# Hooly_2_022.net
KiCad netlist of a schematic drawn in EAGLE
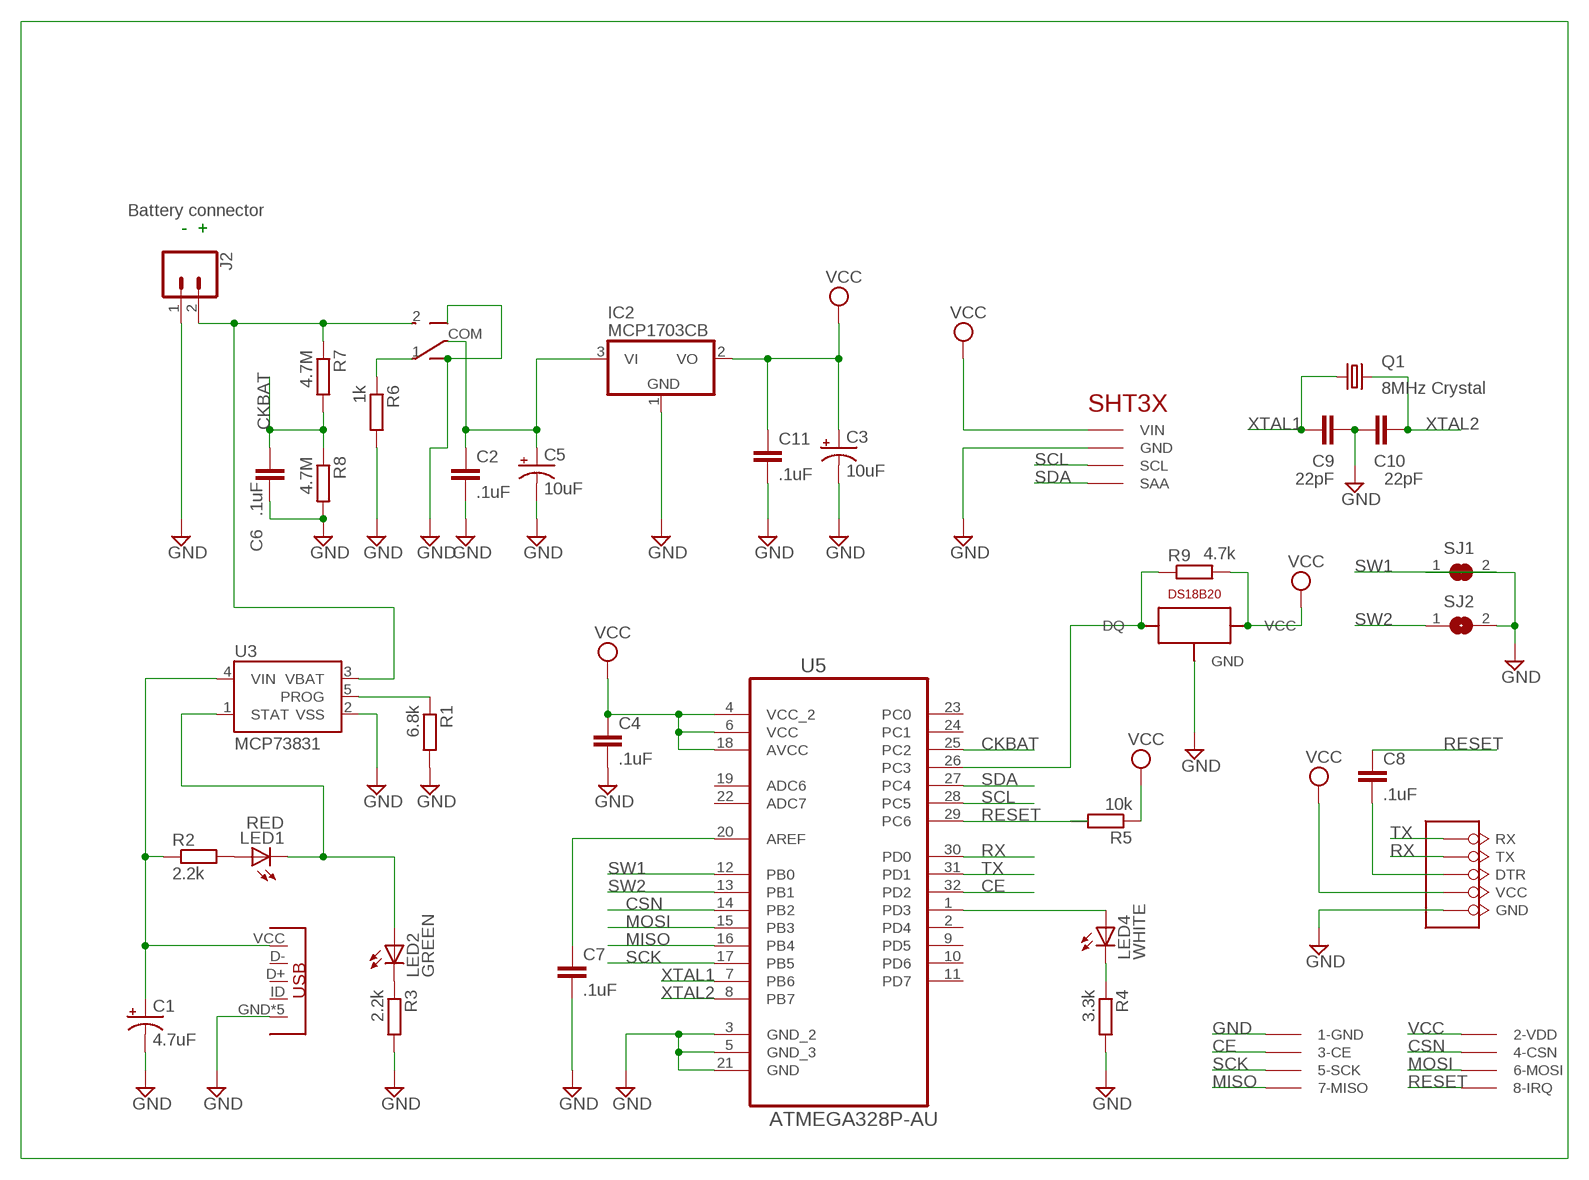
[diagram p0: schematic, sheet 1]

(export (version "E")
  (design (tool "Eeschema 10.0.6"))
  (components
    (comp (ref "C1")
      (value "4.7uF")
      (footprint "eagle-import:CPOL-RADIAL-2.5MM-5MM")
      (libsource (lib "eagle-import") (part "10UF-POLAR-RADIAL-2.5MM-25V-20%"))
    )
    (comp (ref "C2")
      (value ".1uF")
      (footprint "eagle-import:C1206")
      (libsource (lib "eagle-import") (part "resistor_348_C-EUC1206"))
    )
    (comp (ref "C3")
      (value "10uF")
      (footprint "eagle-import:CPOL-RADIAL-2.5MM-5MM")
      (libsource (lib "eagle-import") (part "10UF-POLAR-RADIAL-2.5MM-25V-20%"))
    )
    (comp (ref "C4")
      (value ".1uF")
      (footprint "eagle-import:C1206")
      (libsource (lib "eagle-import") (part "resistor_348_C-EUC1206"))
    )
    (comp (ref "C5")
      (value "10uF")
      (footprint "eagle-import:CPOL-RADIAL-2.5MM-5MM")
      (libsource (lib "eagle-import") (part "10UF-POLAR-RADIAL-2.5MM-25V-20%"))
    )
    (comp (ref "C6")
      (value ".1uF")
      (footprint "eagle-import:C1206")
      (libsource (lib "eagle-import") (part "resistor_348_C-EUC1206"))
    )
    (comp (ref "C7")
      (value ".1uF")
      (footprint "eagle-import:C1206")
      (libsource (lib "eagle-import") (part "resistor_348_C-EUC1206"))
    )
    (comp (ref "C8")
      (value ".1uF")
      (footprint "eagle-import:C1206")
      (libsource (lib "eagle-import") (part "resistor_348_C-EUC1206"))
    )
    (comp (ref "C9")
      (value "22pF")
      (footprint "eagle-import:C0603K")
      (libsource (lib "eagle-import") (part "C-EUC0603K"))
    )
    (comp (ref "C10")
      (value "22pF")
      (footprint "eagle-import:C0603K")
      (libsource (lib "eagle-import") (part "C-EUC0603K"))
    )
    (comp (ref "C11")
      (value ".1uF")
      (footprint "eagle-import:C1206")
      (libsource (lib "eagle-import") (part "resistor_348_C-EUC1206"))
    )
    (comp (ref "IC2")
      (value "MCP1703CB")
      (footprint "eagle-import:SOT23")
      (libsource (lib "eagle-import") (part "MCP1703CB"))
    )
    (comp (ref "J2")
      (value "CONN_02")
      (footprint "eagle-import:1X02")
      (libsource (lib "eagle-import") (part "CONN_02"))
    )
    (comp (ref "LED1")
      (value "RED")
      (footprint "eagle-import:CHIPLED_1206")
      (libsource (lib "eagle-import") (part "LEDCHIPLED_1206"))
    )
    (comp (ref "LED2")
      (value "GREEN")
      (footprint "eagle-import:CHIPLED_1206")
      (libsource (lib "eagle-import") (part "LEDCHIPLED_1206"))
    )
    (comp (ref "LED4")
      (value "WHITE")
      (footprint "eagle-import:CHIPLED_1206")
      (libsource (lib "eagle-import") (part "LEDCHIPLED_1206"))
    )
    (comp (ref "Q1")
      (value "8MHz Crystal")
      (footprint "eagle-import:5.0X3.2_2")
      (libsource (lib "eagle-import") (part "KX-9B"))
    )
    (comp (ref "R1")
      (value "6.8k")
      (footprint "eagle-import:R1206")
      (libsource (lib "eagle-import") (part "R-EU_R1206"))
    )
    (comp (ref "R2")
      (value "2.2k")
      (footprint "eagle-import:R1206")
      (libsource (lib "eagle-import") (part "R-EU_R1206"))
    )
    (comp (ref "R3")
      (value "2.2k")
      (footprint "eagle-import:R1206")
      (libsource (lib "eagle-import") (part "R-EU_R1206"))
    )
    (comp (ref "R4")
      (value "3.3k")
      (footprint "eagle-import:R1206")
      (libsource (lib "eagle-import") (part "R-EU_R1206"))
    )
    (comp (ref "R5")
      (value "10k")
      (footprint "eagle-import:R1206")
      (libsource (lib "eagle-import") (part "R-EU_R1206"))
    )
    (comp (ref "R6")
      (value "1k")
      (footprint "eagle-import:R1206")
      (libsource (lib "eagle-import") (part "R-EU_R1206"))
    )
    (comp (ref "R7")
      (value "4.7M")
      (footprint "eagle-import:R1206")
      (libsource (lib "eagle-import") (part "R-EU_R1206"))
    )
    (comp (ref "R8")
      (value "4.7M")
      (footprint "eagle-import:R1206")
      (libsource (lib "eagle-import") (part "R-EU_R1206"))
    )
    (comp (ref "R9")
      (value "4.7k")
      (footprint "eagle-import:R1206")
      (libsource (lib "eagle-import") (part "R-EU_R1206"))
    )
    (comp (ref "SJ1") (value "SJ") (footprint "eagle-import:SJ") (libsource (lib "eagle-import") (part "SJ")))
    (comp (ref "SJ2") (value "SJ") (footprint "eagle-import:SJ") (libsource (lib "eagle-import") (part "SJ")))
    (comp (ref "U$1")
      (value "SHT3XLARGE")
      (footprint "eagle-import:MYSHT3X")
      (libsource (lib "eagle-import") (part "SHT3XLARGE"))
    )
    (comp (ref "U$2")
      (value "MYSWITCH2MM")
      (footprint "eagle-import:MYSWITCH")
      (libsource (lib "eagle-import") (part "MYSWITCH2MM"))
    )
    (comp (ref "U$3")
      (value "MYDS18B20")
      (footprint "eagle-import:MYDS18B20")
      (libsource (lib "eagle-import") (part "MYDS18B20"))
    )
    (comp (ref "U$4")
      (value "MYNRF24L01SOCKET")
      (footprint "eagle-import:MYNRF24L01SOCKET")
      (libsource (lib "eagle-import") (part "MYNRF24L01SOCKET"))
    )
    (comp (ref "U$6")
      (value "FTDI232")
      (footprint "eagle-import:FTDI232")
      (libsource (lib "eagle-import") (part "FTDI232"))
    )
    (comp (ref "U$7")
      (value "MYMICROUSB")
      (footprint "eagle-import:MYMICROUSB")
      (libsource (lib "eagle-import") (part "MYMICROUSB"))
    )
    (comp (ref "U3")
      (value "MCP73831")
      (footprint "eagle-import:SOT23-5")
      (libsource (lib "eagle-import") (part "MCP73831"))
    )
    (comp (ref "U5")
      (value "ATMEGA328P-AU")
      (footprint "eagle-import:QFP80P900X900X120-32N")
      (libsource (lib "eagle-import") (part "ATMEGA328P-AU"))
    )
  )
  (nets
    (net (code "1") (name "/CE") (class "Default")
      (node (ref "U$4") (pin "CE") (pinfunction "3-CE_CE") (pintype "bidirectional"))
      (node (ref "U5") (pin "32") (pinfunction "PD2_32") (pintype "bidirectional"))
    )
    (net (code "2") (name "/CKBAT") (class "Default")
      (node (ref "C6") (pin "1") (pinfunction "1_1") (pintype "passive"))
      (node (ref "R7") (pin "2") (pinfunction "2_2") (pintype "passive"))
      (node (ref "R8") (pin "1") (pinfunction "1_1") (pintype "passive"))
      (node (ref "U5") (pin "25") (pinfunction "PC2_25") (pintype "bidirectional"))
    )
    (net (code "3") (name "/CSN") (class "Default")
      (node (ref "U$4") (pin "CSN") (pinfunction "4-CSN_CSN") (pintype "bidirectional"))
      (node (ref "U5") (pin "14") (pinfunction "PB2_14") (pintype "bidirectional"))
    )
    (net (code "4") (name "/MISO") (class "Default")
      (node (ref "U$4") (pin "MISO") (pinfunction "7-MISO_MISO") (pintype "bidirectional"))
      (node (ref "U5") (pin "16") (pinfunction "PB4_16") (pintype "bidirectional"))
    )
    (net (code "5") (name "/MOSI") (class "Default")
      (node (ref "U$4") (pin "MOSI") (pinfunction "6-MOSI_MOSI") (pintype "bidirectional"))
      (node (ref "U5") (pin "15") (pinfunction "PB3_15") (pintype "bidirectional"))
    )
    (net (code "6") (name "/RESET") (class "Default")
      (node (ref "C8") (pin "1") (pinfunction "1_1") (pintype "passive"))
      (node (ref "R5") (pin "2") (pinfunction "2_2") (pintype "passive"))
      (node (ref "U$4") (pin "IRQ") (pinfunction "8-IRQ_IRQ") (pintype "bidirectional"))
      (node (ref "U5") (pin "29") (pinfunction "PC6_29") (pintype "bidirectional"))
    )
    (net (code "7") (name "/RX") (class "Default")
      (node (ref "U$6") (pin "TX") (pinfunction "TX_TX") (pintype "bidirectional"))
      (node (ref "U5") (pin "30") (pinfunction "PD0_30") (pintype "bidirectional"))
    )
    (net (code "8") (name "/SCK") (class "Default")
      (node (ref "U$4") (pin "SCK") (pinfunction "5-SCK_SCK") (pintype "bidirectional"))
      (node (ref "U5") (pin "17") (pinfunction "PB5_17") (pintype "bidirectional"))
    )
    (net (code "9") (name "/SCL") (class "Default")
      (node (ref "U$1") (pin "SCL") (pinfunction "SCL_SCL") (pintype "bidirectional"))
      (node (ref "U5") (pin "28") (pinfunction "PC5_28") (pintype "bidirectional"))
    )
    (net (code "10") (name "/SDA") (class "Default")
      (node (ref "U$1") (pin "SAA") (pinfunction "SAA_SAA") (pintype "bidirectional"))
      (node (ref "U5") (pin "27") (pinfunction "PC4_27") (pintype "bidirectional"))
    )
    (net (code "11") (name "/SW1") (class "Default")
      (node (ref "SJ1") (pin "2") (pinfunction "2_2") (pintype "passive"))
      (node (ref "U5") (pin "12") (pinfunction "PB0_12") (pintype "bidirectional"))
    )
    (net (code "12") (name "/SW2") (class "Default")
      (node (ref "SJ2") (pin "1") (pinfunction "1_1") (pintype "passive"))
      (node (ref "U5") (pin "13") (pinfunction "PB1_13") (pintype "bidirectional"))
    )
    (net (code "13") (name "/TX") (class "Default")
      (node (ref "U$6") (pin "RX") (pinfunction "RX_RX") (pintype "bidirectional"))
      (node (ref "U5") (pin "31") (pinfunction "PD1_31") (pintype "bidirectional"))
    )
    (net (code "14") (name "/XTAL1") (class "Default")
      (node (ref "C9") (pin "1") (pinfunction "1_1") (pintype "passive"))
      (node (ref "Q1") (pin "1") (pinfunction "1_1") (pintype "passive"))
      (node (ref "U5") (pin "7") (pinfunction "PB6_7") (pintype "bidirectional"))
    )
    (net (code "15") (name "/XTAL2") (class "Default")
      (node (ref "C10") (pin "2") (pinfunction "2_2") (pintype "passive"))
      (node (ref "Q1") (pin "2") (pinfunction "2_2") (pintype "passive"))
      (node (ref "U5") (pin "8") (pinfunction "PB7_8") (pintype "bidirectional"))
    )
    (net (code "16") (name "GND") (class "Default")
      (node (ref "C1") (pin "2") (pinfunction "-_2") (pintype "passive"))
      (node (ref "C10") (pin "1") (pinfunction "1_1") (pintype "passive"))
      (node (ref "C11") (pin "2") (pinfunction "2_2") (pintype "passive"))
      (node (ref "C2") (pin "2") (pinfunction "2_2") (pintype "passive"))
      (node (ref "C3") (pin "2") (pinfunction "-_2") (pintype "passive"))
      (node (ref "C4") (pin "2") (pinfunction "2_2") (pintype "passive"))
      (node (ref "C5") (pin "2") (pinfunction "-_2") (pintype "passive"))
      (node (ref "C6") (pin "2") (pinfunction "2_2") (pintype "passive"))
      (node (ref "C7") (pin "2") (pinfunction "2_2") (pintype "passive"))
      (node (ref "C9") (pin "2") (pinfunction "2_2") (pintype "passive"))
      (node (ref "IC2") (pin "1") (pinfunction "GND_1") (pintype "passive"))
      (node (ref "J2") (pin "1") (pinfunction "1_1") (pintype "passive"))
      (node (ref "R1") (pin "2") (pinfunction "2_2") (pintype "passive"))
      (node (ref "R3") (pin "2") (pinfunction "2_2") (pintype "passive"))
      (node (ref "R4") (pin "2") (pinfunction "2_2") (pintype "passive"))
      (node (ref "R6") (pin "2") (pinfunction "2_2") (pintype "passive"))
      (node (ref "R8") (pin "2") (pinfunction "2_2") (pintype "passive"))
      (node (ref "SJ1") (pin "1") (pinfunction "1_1") (pintype "passive"))
      (node (ref "SJ2") (pin "2") (pinfunction "2_2") (pintype "passive"))
      (node (ref "U$1") (pin "GND") (pinfunction "GND_GND") (pintype "bidirectional"))
      (node (ref "U$2") (pin "GND1") (pinfunction "GND1_GND1") (pintype "bidirectional"))
      (node (ref "U$2") (pin "GND2") (pinfunction "GND2_GND2") (pintype "bidirectional"))
      (node (ref "U$3") (pin "GND") (pinfunction "GND_GND") (pintype "bidirectional"))
      (node (ref "U$4") (pin "GND") (pinfunction "1-GND_GND") (pintype "bidirectional"))
      (node (ref "U$6") (pin "GND") (pinfunction "GND_GND") (pintype "bidirectional"))
      (node (ref "U$7") (pin "GND") (pinfunction "GND_GND") (pintype "bidirectional"))
      (node (ref "U$7") (pin "P$6") (pinfunction "GND_P$6") (pintype "bidirectional"))
      (node (ref "U$7") (pin "P$7") (pinfunction "GND_P$7") (pintype "bidirectional"))
      (node (ref "U$7") (pin "P$8") (pinfunction "GND_P$8") (pintype "bidirectional"))
      (node (ref "U$7") (pin "P$9") (pinfunction "GND_P$9") (pintype "bidirectional"))
      (node (ref "U3") (pin "2") (pinfunction "VSS_2") (pintype "power_in"))
      (node (ref "U5") (pin "21") (pinfunction "GND_21") (pintype "passive"))
      (node (ref "U5") (pin "3") (pinfunction "GND_2_3") (pintype "passive"))
      (node (ref "U5") (pin "5") (pinfunction "GND_3_5") (pintype "passive"))
    )
    (net (code "17") (name "Net-(C1-+)") (class "Default")
      (node (ref "C1") (pin "1") (pinfunction "+_1") (pintype "passive"))
      (node (ref "R2") (pin "1") (pinfunction "1_1") (pintype "passive"))
      (node (ref "U$7") (pin "VCC") (pinfunction "VCC_VCC") (pintype "bidirectional"))
      (node (ref "U3") (pin "4") (pinfunction "VIN_4") (pintype "power_in"))
    )
    (net (code "18") (name "Net-(C5-+)") (class "Default")
      (node (ref "C2") (pin "1") (pinfunction "1_1") (pintype "passive"))
      (node (ref "C5") (pin "1") (pinfunction "+_1") (pintype "passive"))
      (node (ref "IC2") (pin "3") (pinfunction "VI_3") (pintype "input"))
      (node (ref "U$2") (pin "COM") (pinfunction "COM_COM") (pintype "bidirectional"))
    )
    (net (code "19") (name "Net-(C8-Pad2)") (class "Default")
      (node (ref "C8") (pin "2") (pinfunction "2_2") (pintype "passive"))
      (node (ref "U$6") (pin "DTR") (pinfunction "DTR_DTR") (pintype "bidirectional"))
    )
    (net (code "20") (name "Net-(LED1-PadA)") (class "Default")
      (node (ref "LED1") (pin "A") (pinfunction "A_A") (pintype "passive"))
      (node (ref "R2") (pin "2") (pinfunction "2_2") (pintype "passive"))
    )
    (net (code "21") (name "Net-(LED2-PadC)") (class "Default")
      (node (ref "LED2") (pin "C") (pinfunction "C_C") (pintype "passive"))
      (node (ref "R3") (pin "1") (pinfunction "1_1") (pintype "passive"))
    )
    (net (code "22") (name "Net-(LED4-PadC)") (class "Default")
      (node (ref "LED4") (pin "C") (pinfunction "C_C") (pintype "passive"))
      (node (ref "R4") (pin "1") (pinfunction "1_1") (pintype "passive"))
    )
    (net (code "23") (name "Net-(R6-Pad1)") (class "Default")
      (node (ref "R6") (pin "1") (pinfunction "1_1") (pintype "passive"))
      (node (ref "U$2") (pin "1") (pinfunction "1_1") (pintype "bidirectional"))
    )
    (net (code "24") (name "Net-(U3-PROG)") (class "Default")
      (node (ref "R1") (pin "1") (pinfunction "1_1") (pintype "passive"))
      (node (ref "U3") (pin "5") (pinfunction "PROG_5") (pintype "input"))
    )
    (net (code "25") (name "Net-(U3-STAT)") (class "Default")
      (node (ref "LED1") (pin "C") (pinfunction "C_C") (pintype "passive"))
      (node (ref "LED2") (pin "A") (pinfunction "A_A") (pintype "passive"))
      (node (ref "U3") (pin "1") (pinfunction "STAT_1") (pintype "output"))
    )
    (net (code "26") (name "Net-(U3-VBAT)") (class "Default")
      (node (ref "J2") (pin "2") (pinfunction "2_2") (pintype "passive"))
      (node (ref "R7") (pin "1") (pinfunction "1_1") (pintype "passive"))
      (node (ref "U$2") (pin "2") (pinfunction "2_2") (pintype "bidirectional"))
      (node (ref "U3") (pin "3") (pinfunction "VBAT_3") (pintype "power_in"))
    )
    (net (code "27") (name "Net-(U5-AREF)") (class "Default")
      (node (ref "C7") (pin "1") (pinfunction "1_1") (pintype "passive"))
      (node (ref "U5") (pin "20") (pinfunction "AREF_20") (pintype "input"))
    )
    (net (code "28") (name "Net-(U5-PC3)") (class "Default")
      (node (ref "R9") (pin "1") (pinfunction "1_1") (pintype "passive"))
      (node (ref "U$3") (pin "DQ") (pinfunction "DQ_DQ") (pintype "bidirectional"))
      (node (ref "U5") (pin "26") (pinfunction "PC3_26") (pintype "bidirectional"))
    )
    (net (code "29") (name "Net-(U5-PD3)") (class "Default")
      (node (ref "LED4") (pin "A") (pinfunction "A_A") (pintype "passive"))
      (node (ref "U5") (pin "1") (pinfunction "PD3_1") (pintype "bidirectional"))
    )
    (net (code "30") (name "VCC") (class "Default")
      (node (ref "C11") (pin "1") (pinfunction "1_1") (pintype "passive"))
      (node (ref "C3") (pin "1") (pinfunction "+_1") (pintype "passive"))
      (node (ref "C4") (pin "1") (pinfunction "1_1") (pintype "passive"))
      (node (ref "IC2") (pin "2") (pinfunction "VO_2") (pintype "passive"))
      (node (ref "R5") (pin "1") (pinfunction "1_1") (pintype "passive"))
      (node (ref "R9") (pin "2") (pinfunction "2_2") (pintype "passive"))
      (node (ref "U$1") (pin "VIN") (pinfunction "VIN_VIN") (pintype "bidirectional"))
      (node (ref "U$3") (pin "VCC") (pinfunction "VCC_VCC") (pintype "bidirectional"))
      (node (ref "U$4") (pin "VDD") (pinfunction "2-VDD_VDD") (pintype "bidirectional"))
      (node (ref "U$6") (pin "VCC") (pinfunction "VCC_VCC") (pintype "bidirectional"))
      (node (ref "U5") (pin "18") (pinfunction "AVCC_18") (pintype "power_in"))
      (node (ref "U5") (pin "4") (pinfunction "VCC_2_4") (pintype "power_in"))
      (node (ref "U5") (pin "6") (pinfunction "VCC_6") (pintype "power_in"))
    )
    (net (code "31") (name "unconnected-(U$7-PadD+)") (class "Default")
      (node (ref "U$7") (pin "D+") (pinfunction "D+_D+") (pintype "bidirectional"))
    )
    (net (code "32") (name "unconnected-(U$7-PadD-)") (class "Default")
      (node (ref "U$7") (pin "D-") (pinfunction "D-_D-") (pintype "bidirectional"))
    )
    (net (code "33") (name "unconnected-(U$7-PadID)") (class "Default")
      (node (ref "U$7") (pin "ID") (pinfunction "ID_ID") (pintype "bidirectional"))
    )
    (net (code "34") (name "unconnected-(U5-ADC6-Pad19)") (class "Default")
      (node (ref "U5") (pin "19") (pinfunction "ADC6_19") (pintype "input"))
    )
    (net (code "35") (name "unconnected-(U5-ADC7-Pad22)") (class "Default")
      (node (ref "U5") (pin "22") (pinfunction "ADC7_22") (pintype "input"))
    )
    (net (code "36") (name "unconnected-(U5-PC0-Pad23)") (class "Default")
      (node (ref "U5") (pin "23") (pinfunction "PC0_23") (pintype "bidirectional"))
    )
    (net (code "37") (name "unconnected-(U5-PC1-Pad24)") (class "Default")
      (node (ref "U5") (pin "24") (pinfunction "PC1_24") (pintype "bidirectional"))
    )
    (net (code "38") (name "unconnected-(U5-PD4-Pad2)") (class "Default")
      (node (ref "U5") (pin "2") (pinfunction "PD4_2") (pintype "bidirectional"))
    )
    (net (code "39") (name "unconnected-(U5-PD5-Pad9)") (class "Default")
      (node (ref "U5") (pin "9") (pinfunction "PD5_9") (pintype "bidirectional"))
    )
    (net (code "40") (name "unconnected-(U5-PD6-Pad10)") (class "Default")
      (node (ref "U5") (pin "10") (pinfunction "PD6_10") (pintype "bidirectional"))
    )
    (net (code "41") (name "unconnected-(U5-PD7-Pad11)") (class "Default")
      (node (ref "U5") (pin "11") (pinfunction "PD7_11") (pintype "bidirectional"))
    )
  )
)
